# LCmeter0-LCD-8pinlcd-alt.net
KiCad netlist of a schematic drawn in EAGLE
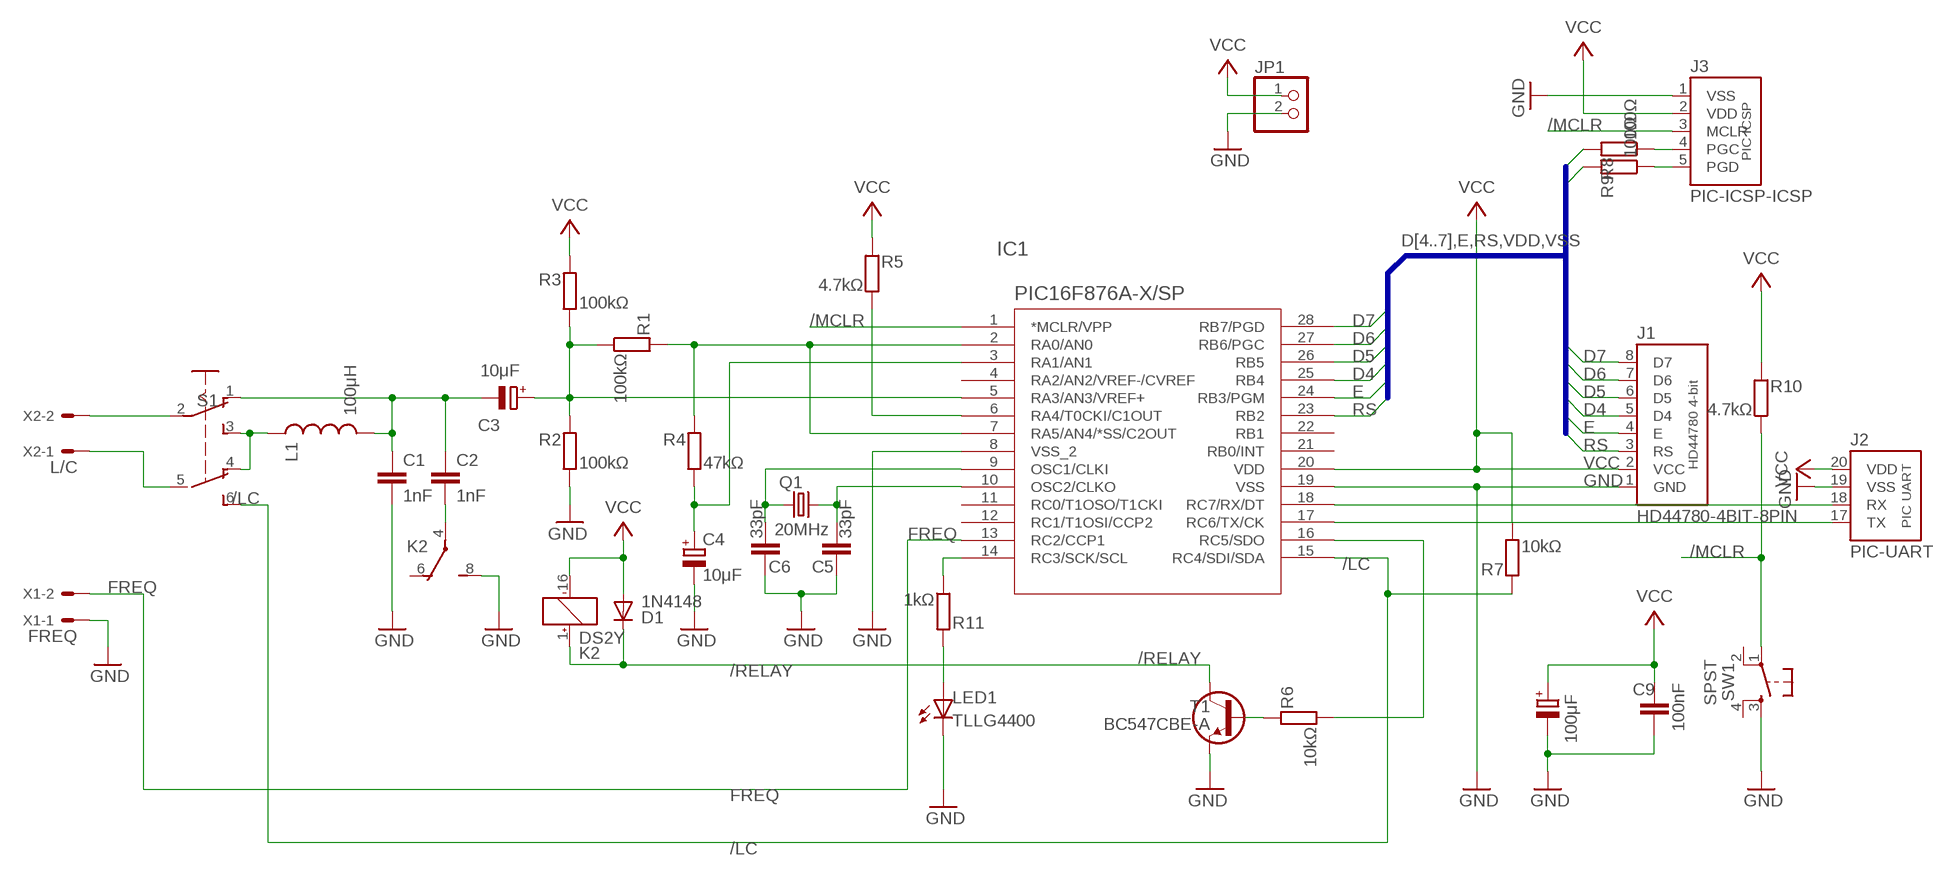
[diagram p0: schematic, sheet 1]

(export (version "E")
  (design (tool "Eeschema 10.0.6"))
  (components
    (comp (ref "C1")
      (value "1nF")
      (footprint "eagle-import:C050-020X036")
      (libsource (lib "eagle-import") (part "C050-020X036"))
    )
    (comp (ref "C2")
      (value "1nF")
      (footprint "eagle-import:C050-020X036")
      (libsource (lib "eagle-import") (part "C050-020X036"))
    )
    (comp (ref "C3")
      (value "10μF")
      (footprint "eagle-import:E5-4")
      (libsource (lib "eagle-import") (part "CPOLE5-4"))
    )
    (comp (ref "C4")
      (value "10μF")
      (footprint "eagle-import:E5-4")
      (libsource (lib "eagle-import") (part "CPOLE5-4"))
    )
    (comp (ref "C5")
      (value "33pF")
      (footprint "eagle-import:C025-020X036")
      (libsource (lib "eagle-import") (part "C025-020X036"))
    )
    (comp (ref "C6")
      (value "33pF")
      (footprint "eagle-import:C025-020X036")
      (libsource (lib "eagle-import") (part "C025-020X036"))
    )
    (comp (ref "C7")
      (value "100μF")
      (footprint "eagle-import:E2,5-6")
      (libsource (lib "eagle-import") (part "CPOLE2.5-6"))
    )
    (comp (ref "C9")
      (value "100nF")
      (footprint "eagle-import:C025-024X044")
      (libsource (lib "eagle-import") (part "C-EU025-024X044"))
    )
    (comp (ref "D1")
      (value "1N4148")
      (footprint "eagle-import:DO34-7")
      (libsource (lib "eagle-import") (part "1N414834-7"))
    )
    (comp (ref "IC1")
      (value "PIC16F876A-X/SP")
      (footprint "eagle-import:DIL28-3")
      (libsource (lib "eagle-import") (part "PIC16F876A-X/SP"))
    )
    (comp (ref "J1")
      (value "HD44780-4BIT-8PIN")
      (footprint "eagle-import:CONN-8P")
      (libsource (lib "eagle-import") (part "HD44780-4BIT-8PIN"))
    )
    (comp (ref "J2")
      (value "PIC-UART")
      (footprint "eagle-import:PIC-UART")
      (libsource (lib "eagle-import") (part "PIC-UART"))
    )
    (comp (ref "J3")
      (value "PIC-ICSP-ICSP")
      (footprint "eagle-import:PIC-ICSP")
      (libsource (lib "eagle-import") (part "PIC-ICSP-ICSP"))
    )
    (comp (ref "JP1")
      (value "PINHD-1X2")
      (footprint "eagle-import:1X02")
      (libsource (lib "eagle-import") (part "PINHD-1X2"))
    )
    (comp (ref "K2")
      (value "DS2Y")
      (footprint "eagle-import:DS2Y")
      (fields (field (name "MPN") "DS2Y-S-DC5V"))
      (libsource (lib "eagle-import") (part "DS2Y-S-DC5V"))
    )
    (comp (ref "L1")
      (value "100μH")
      (footprint "eagle-import:L-02_7")
      (libsource (lib "eagle-import") (part "L02/7"))
    )
    (comp (ref "LED1")
      (value "TLLG4400")
      (footprint "eagle-import:LED3MM")
      (fields (field (name "MF") "VISHAY SEMICONDUCTOR"))
      (libsource (lib "eagle-import") (part "TLLG4400"))
    )
    (comp (ref "Q1")
      (value "20MHz")
      (footprint "eagle-import:HC49")
      (libsource (lib "eagle-import") (part "CRYSTALHC49"))
    )
    (comp (ref "R1")
      (value "100kΩ")
      (footprint "eagle-import:0202_7")
      (libsource (lib "eagle-import") (part "R0202/7"))
    )
    (comp (ref "R2")
      (value "100kΩ")
      (footprint "eagle-import:0202_7")
      (libsource (lib "eagle-import") (part "R0202/7"))
    )
    (comp (ref "R3")
      (value "100kΩ")
      (footprint "eagle-import:0202_7")
      (libsource (lib "eagle-import") (part "R0202/7"))
    )
    (comp (ref "R4")
      (value "47kΩ")
      (footprint "eagle-import:0202_7")
      (libsource (lib "eagle-import") (part "R0202/7"))
    )
    (comp (ref "R5")
      (value "4.7kΩ")
      (footprint "eagle-import:0202_7")
      (libsource (lib "eagle-import") (part "R0202/7"))
    )
    (comp (ref "R6")
      (value "10kΩ")
      (footprint "eagle-import:0202_7")
      (libsource (lib "eagle-import") (part "R0202/7"))
    )
    (comp (ref "R7")
      (value "10kΩ")
      (footprint "eagle-import:0202_10")
      (libsource (lib "eagle-import") (part "R0202/10"))
    )
    (comp (ref "R8")
      (value "100Ω")
      (footprint "eagle-import:0202_5")
      (libsource (lib "eagle-import") (part "R0202/5"))
    )
    (comp (ref "R9")
      (value "100Ω")
      (footprint "eagle-import:0202_5")
      (libsource (lib "eagle-import") (part "R0202/5"))
    )
    (comp (ref "R10")
      (value "4.7kΩ")
      (footprint "eagle-import:0202_7")
      (libsource (lib "eagle-import") (part "R0202/7"))
    )
    (comp (ref "R11")
      (value "1kΩ")
      (footprint "eagle-import:0202_5")
      (libsource (lib "eagle-import") (part "R0202/5"))
    )
    (comp (ref "S1")
      (value "SL-SW-2P-2T")
      (footprint "eagle-import:SLSW-2P2T")
      (libsource (lib "eagle-import") (part "SL-SW-2P-2T"))
    )
    (comp (ref "SW1")
      (value "SPST")
      (footprint "eagle-import:PB-5")
      (libsource (lib "eagle-import") (part "PB-SPST"))
    )
    (comp (ref "T1")
      (value "BC547CBE-A")
      (footprint "eagle-import:TO92-CBE-A")
      (libsource (lib "eagle-import") (part "BC547CBE-A"))
    )
    (comp (ref "X1")
      (value "FREQ")
      (footprint "eagle-import:70543-02")
      (libsource (lib "eagle-import") (part "C-GRID-02-70543"))
    )
    (comp (ref "X2")
      (value "L/C")
      (footprint "eagle-import:70543-02")
      (libsource (lib "eagle-import") (part "C-GRID-02-70543"))
    )
  )
  (nets
    (net (code "3") (name "/D4") (class "Default")
      (node (ref "IC1") (pin "25") (pinfunction "RB4_25") (pintype "passive"))
      (node (ref "J1") (pin "5") (pinfunction "D4_5") (pintype "passive"))
    )
    (net (code "4") (name "/D5") (class "Default")
      (node (ref "IC1") (pin "26") (pinfunction "RB5_26") (pintype "passive"))
      (node (ref "J1") (pin "6") (pinfunction "D5_6") (pintype "passive"))
    )
    (net (code "5") (name "/D6") (class "Default")
      (node (ref "IC1") (pin "27") (pinfunction "RB6/PGC_27") (pintype "passive"))
      (node (ref "J1") (pin "7") (pinfunction "D6_7") (pintype "passive"))
      (node (ref "R9") (pin "2") (pinfunction "2_2") (pintype "passive"))
    )
    (net (code "6") (name "/D7") (class "Default")
      (node (ref "IC1") (pin "28") (pinfunction "RB7/PGD_28") (pintype "passive"))
      (node (ref "J1") (pin "8") (pinfunction "D7_8") (pintype "passive"))
      (node (ref "R8") (pin "2") (pinfunction "2_2") (pintype "passive"))
    )
    (net (code "7") (name "/E") (class "Default")
      (node (ref "IC1") (pin "24") (pinfunction "RB3/PGM_24") (pintype "passive"))
      (node (ref "J1") (pin "4") (pinfunction "E_4") (pintype "passive"))
    )
    (net (code "8") (name "/FREQ") (class "Default")
      (node (ref "IC1") (pin "13") (pinfunction "RC2/CCP1_13") (pintype "passive"))
      (node (ref "X1") (pin "2") (pinfunction "S_2") (pintype "passive"))
    )
    (net (code "9") (name "/RS") (class "Default")
      (node (ref "IC1") (pin "23") (pinfunction "RB2_23") (pintype "passive"))
      (node (ref "J1") (pin "3") (pinfunction "RS_3") (pintype "passive"))
    )
    (net (code "11") (name "/{slash}LC") (class "Default")
      (node (ref "IC1") (pin "15") (pinfunction "RC4/SDI/SDA_15") (pintype "passive"))
      (node (ref "R7") (pin "2") (pinfunction "2_2") (pintype "passive"))
      (node (ref "S1") (pin "6") (pinfunction "S1_6") (pintype "passive"))
    )
    (net (code "12") (name "/{slash}MCLR") (class "Default")
      (node (ref "IC1") (pin "1") (pinfunction "*MCLR/VPP_1") (pintype "passive"))
      (node (ref "J3") (pin "3") (pinfunction "MCLR_3") (pintype "passive"))
      (node (ref "R10") (pin "1") (pinfunction "1_1") (pintype "passive"))
      (node (ref "SW1") (pin "1") (pinfunction "P_1") (pintype "passive"))
    )
    (net (code "13") (name "/{slash}RELAY") (class "Default")
      (node (ref "D1") (pin "C") (pinfunction "C_C") (pintype "passive"))
      (node (ref "K2") (pin "1") (pinfunction "+_1") (pintype "passive"))
      (node (ref "T1") (pin "C") (pinfunction "C_C") (pintype "passive"))
    )
    (net (code "14") (name "GND") (class "Default")
      (node (ref "C1") (pin "2") (pinfunction "2_2") (pintype "passive"))
      (node (ref "C4") (pin "-") (pinfunction "-_-") (pintype "passive"))
      (node (ref "C5") (pin "1") (pinfunction "1_1") (pintype "passive"))
      (node (ref "C6") (pin "1") (pinfunction "1_1") (pintype "passive"))
      (node (ref "C7") (pin "-") (pinfunction "-_-") (pintype "passive"))
      (node (ref "C9") (pin "2") (pinfunction "2_2") (pintype "passive"))
      (node (ref "IC1") (pin "19") (pinfunction "VSS_19") (pintype "passive"))
      (node (ref "IC1") (pin "8") (pinfunction "VSS_2_8") (pintype "passive"))
      (node (ref "J1") (pin "1") (pinfunction "GND_1") (pintype "passive"))
      (node (ref "J2") (pin "19") (pinfunction "VSS_19") (pintype "passive"))
      (node (ref "J3") (pin "1") (pinfunction "VSS_1") (pintype "passive"))
      (node (ref "JP1") (pin "2") (pinfunction "2_2") (pintype "passive"))
      (node (ref "K2") (pin "8") (pinfunction "S_8") (pintype "passive"))
      (node (ref "LED1") (pin "K") (pinfunction "C_K") (pintype "passive"))
      (node (ref "R2") (pin "1") (pinfunction "1_1") (pintype "passive"))
      (node (ref "SW1") (pin "3") (pinfunction "S_3") (pintype "passive"))
      (node (ref "T1") (pin "E") (pinfunction "E_E") (pintype "passive"))
      (node (ref "X1") (pin "1") (pinfunction "S_1") (pintype "passive"))
    )
    (net (code "15") (name "Net-(IC1-OSC1{slash}CLKI)") (class "Default")
      (node (ref "C6") (pin "2") (pinfunction "2_2") (pintype "passive"))
      (node (ref "IC1") (pin "9") (pinfunction "OSC1/CLKI_9") (pintype "passive"))
      (node (ref "Q1") (pin "1") (pinfunction "1_1") (pintype "passive"))
    )
    (net (code "16") (name "Net-(IC1-OSC2{slash}CLKO)") (class "Default")
      (node (ref "C5") (pin "2") (pinfunction "2_2") (pintype "passive"))
      (node (ref "IC1") (pin "10") (pinfunction "OSC2/CLKO_10") (pintype "passive"))
      (node (ref "Q1") (pin "2") (pinfunction "2_2") (pintype "passive"))
    )
    (net (code "17") (name "Net-(IC1-RA0{slash}AN0)") (class "Default")
      (node (ref "IC1") (pin "2") (pinfunction "RA0/AN0_2") (pintype "passive"))
      (node (ref "IC1") (pin "7") (pinfunction "RA5/AN4/*SS/C2OUT_7") (pintype "passive"))
      (node (ref "R1") (pin "2") (pinfunction "2_2") (pintype "passive"))
      (node (ref "R4") (pin "2") (pinfunction "2_2") (pintype "passive"))
    )
    (net (code "18") (name "Net-(IC1-RA1{slash}AN1)") (class "Default")
      (node (ref "C4") (pin "+") (pinfunction "+_+") (pintype "passive"))
      (node (ref "IC1") (pin "3") (pinfunction "RA1/AN1_3") (pintype "passive"))
      (node (ref "R4") (pin "1") (pinfunction "1_1") (pintype "passive"))
    )
    (net (code "19") (name "Net-(IC1-RA3{slash}AN3{slash}VREF+)") (class "Default")
      (node (ref "C3") (pin "+") (pinfunction "+_+") (pintype "passive"))
      (node (ref "IC1") (pin "5") (pinfunction "RA3/AN3/VREF+_5") (pintype "passive"))
      (node (ref "R1") (pin "1") (pinfunction "1_1") (pintype "passive"))
      (node (ref "R2") (pin "2") (pinfunction "2_2") (pintype "passive"))
      (node (ref "R3") (pin "1") (pinfunction "1_1") (pintype "passive"))
    )
    (net (code "20") (name "Net-(IC1-RA4{slash}T0CKI{slash}C1OUT)") (class "Default")
      (node (ref "IC1") (pin "6") (pinfunction "RA4/T0CKI/C1OUT_6") (pintype "passive"))
      (node (ref "R5") (pin "1") (pinfunction "1_1") (pintype "passive"))
    )
    (net (code "21") (name "Net-(IC1-RC3{slash}SCK{slash}SCL)") (class "Default")
      (node (ref "IC1") (pin "14") (pinfunction "RC3/SCK/SCL_14") (pintype "passive"))
      (node (ref "R11") (pin "1") (pinfunction "1_1") (pintype "passive"))
    )
    (net (code "22") (name "Net-(IC1-RC5{slash}SDO)") (class "Default")
      (node (ref "IC1") (pin "16") (pinfunction "RC5/SDO_16") (pintype "passive"))
      (node (ref "R6") (pin "1") (pinfunction "1_1") (pintype "passive"))
    )
    (net (code "23") (name "Net-(IC1-RC6{slash}TX{slash}CK)") (class "Default")
      (node (ref "IC1") (pin "17") (pinfunction "RC6/TX/CK_17") (pintype "passive"))
      (node (ref "J2") (pin "17") (pinfunction "TX_17") (pintype "passive"))
    )
    (net (code "24") (name "Net-(IC1-RC7{slash}RX{slash}DT)") (class "Default")
      (node (ref "IC1") (pin "18") (pinfunction "RC7/RX/DT_18") (pintype "passive"))
      (node (ref "J2") (pin "18") (pinfunction "RX_18") (pintype "passive"))
    )
    (net (code "25") (name "Net-(J3-PGC)") (class "Default")
      (node (ref "J3") (pin "4") (pinfunction "PGC_4") (pintype "passive"))
      (node (ref "R8") (pin "1") (pinfunction "1_1") (pintype "passive"))
    )
    (net (code "26") (name "Net-(J3-PGD)") (class "Default")
      (node (ref "J3") (pin "5") (pinfunction "PGD_5") (pintype "passive"))
      (node (ref "R9") (pin "1") (pinfunction "1_1") (pintype "passive"))
    )
    (net (code "27") (name "Net-(K2B-P)") (class "Default")
      (node (ref "C2") (pin "2") (pinfunction "2_2") (pintype "passive"))
      (node (ref "K2") (pin "4") (pinfunction "P_4") (pintype "passive"))
    )
    (net (code "28") (name "Net-(LED1-PadA)") (class "Default")
      (node (ref "LED1") (pin "A") (pinfunction "A_A") (pintype "passive"))
      (node (ref "R11") (pin "2") (pinfunction "2_2") (pintype "passive"))
    )
    (net (code "29") (name "Net-(R6-Pad2)") (class "Default")
      (node (ref "R6") (pin "2") (pinfunction "2_2") (pintype "passive"))
      (node (ref "T1") (pin "B") (pinfunction "B_B") (pintype "passive"))
    )
    (net (code "30") (name "Net-(S1-O)") (class "Default")
      (node (ref "C1") (pin "1") (pinfunction "1_1") (pintype "passive"))
      (node (ref "C2") (pin "1") (pinfunction "1_1") (pintype "passive"))
      (node (ref "C3") (pin "-") (pinfunction "-_-") (pintype "passive"))
      (node (ref "L1") (pin "2") (pinfunction "2_2") (pintype "passive"))
      (node (ref "S1") (pin "1") (pinfunction "O_1") (pintype "passive"))
    )
    (net (code "31") (name "Net-(S1-O1)") (class "Default")
      (node (ref "L1") (pin "1") (pinfunction "1_1") (pintype "passive"))
      (node (ref "S1") (pin "3") (pinfunction "S_3") (pintype "passive"))
      (node (ref "S1") (pin "4") (pinfunction "O1_4") (pintype "passive"))
    )
    (net (code "32") (name "Net-(S1-P)") (class "Default")
      (node (ref "S1") (pin "2") (pinfunction "P_2") (pintype "passive"))
      (node (ref "X2") (pin "2") (pinfunction "S_2") (pintype "passive"))
    )
    (net (code "33") (name "Net-(S1-P1)") (class "Default")
      (node (ref "S1") (pin "5") (pinfunction "P1_5") (pintype "passive"))
      (node (ref "X2") (pin "1") (pinfunction "S_1") (pintype "passive"))
    )
    (net (code "34") (name "VCC") (class "Default")
      (node (ref "C7") (pin "+") (pinfunction "+_+") (pintype "passive"))
      (node (ref "C9") (pin "1") (pinfunction "1_1") (pintype "passive"))
      (node (ref "D1") (pin "A") (pinfunction "A_A") (pintype "passive"))
      (node (ref "IC1") (pin "20") (pinfunction "VDD_20") (pintype "passive"))
      (node (ref "J1") (pin "2") (pinfunction "VCC_2") (pintype "passive"))
      (node (ref "J2") (pin "20") (pinfunction "VDD_20") (pintype "passive"))
      (node (ref "J3") (pin "2") (pinfunction "VDD_2") (pintype "passive"))
      (node (ref "JP1") (pin "1") (pinfunction "1_1") (pintype "passive"))
      (node (ref "K2") (pin "16") (pinfunction "-_16") (pintype "passive"))
      (node (ref "R10") (pin "2") (pinfunction "2_2") (pintype "passive"))
      (node (ref "R3") (pin "2") (pinfunction "2_2") (pintype "passive"))
      (node (ref "R5") (pin "2") (pinfunction "2_2") (pintype "passive"))
      (node (ref "R7") (pin "1") (pinfunction "1_1") (pintype "passive"))
    )
    (net (code "35") (name "unconnected-(IC1-RA2{slash}AN2{slash}VREF-{slash}CVREF-Pad4)") (class "Default")
      (node (ref "IC1") (pin "4") (pinfunction "RA2/AN2/VREF-/CVREF_4") (pintype "passive"))
    )
    (net (code "36") (name "unconnected-(IC1-RB0{slash}INT-Pad21)") (class "Default")
      (node (ref "IC1") (pin "21") (pinfunction "RB0/INT_21") (pintype "passive"))
    )
    (net (code "37") (name "unconnected-(IC1-RB1-Pad22)") (class "Default")
      (node (ref "IC1") (pin "22") (pinfunction "RB1_22") (pintype "passive"))
    )
    (net (code "38") (name "unconnected-(IC1-RC0{slash}T1OSO{slash}T1CKI-Pad11)") (class "Default")
      (node (ref "IC1") (pin "11") (pinfunction "RC0/T1OSO/T1CKI_11") (pintype "passive"))
    )
    (net (code "39") (name "unconnected-(IC1-RC1{slash}T1OSI{slash}CCP2-Pad12)") (class "Default")
      (node (ref "IC1") (pin "12") (pinfunction "RC1/T1OSI/CCP2_12") (pintype "passive"))
    )
    (net (code "40") (name "unconnected-(K2B-O-Pad6)") (class "Default")
      (node (ref "K2") (pin "6") (pinfunction "O_6") (pintype "passive"))
    )
    (net (code "41") (name "unconnected-(SW1-P1-Pad2)") (class "Default")
      (node (ref "SW1") (pin "2") (pinfunction "P1_2") (pintype "passive"))
    )
    (net (code "42") (name "unconnected-(SW1-S1-Pad4)") (class "Default")
      (node (ref "SW1") (pin "4") (pinfunction "S1_4") (pintype "passive"))
    )
  )
)
